# pcb_v1_mod.net
KiCad netlist of a schematic drawn in EAGLE
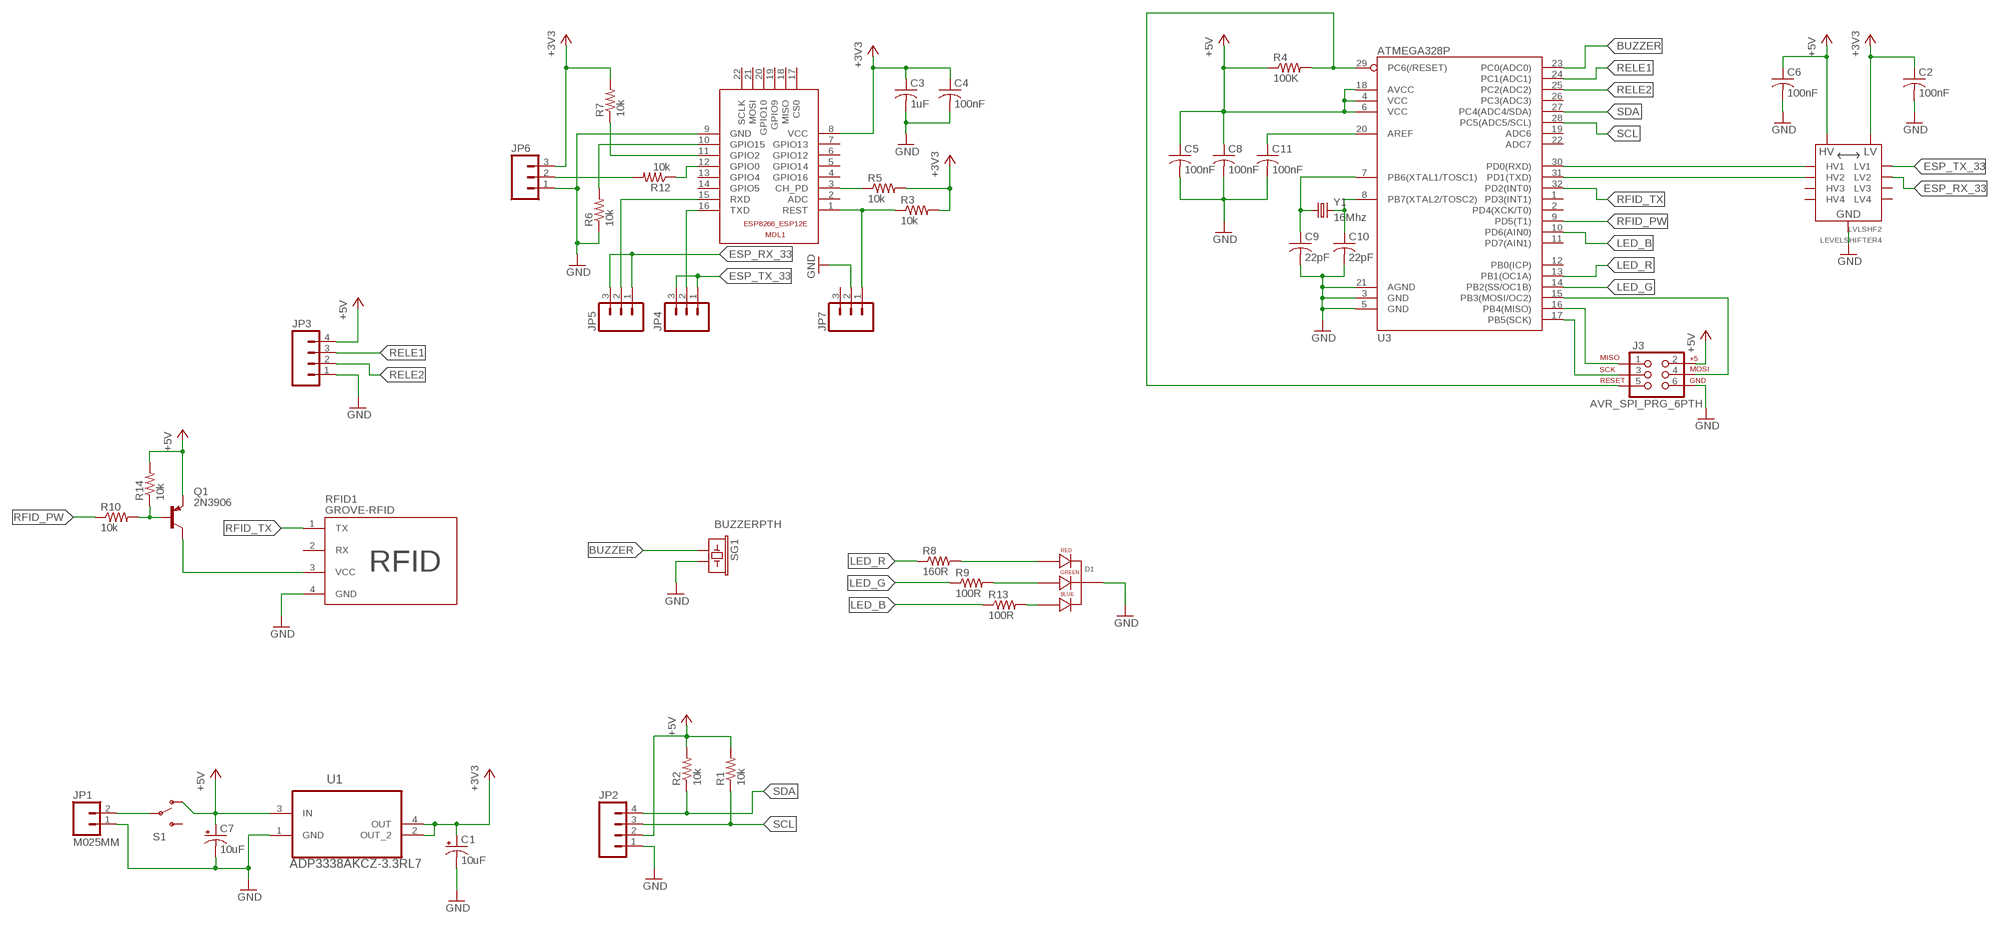
[diagram p0: schematic, sheet 1]

(export (version "E")
  (design (tool "Eeschema 10.0.6"))
  (components
    (comp (ref "C1")
      (value "10uF")
      (footprint "eagle-import:E2,5-6")
      (libsource (lib "eagle-import") (part "CPOL-USE2.5-6"))
    )
    (comp (ref "C2")
      (value "100nF")
      (footprint "eagle-import:C0805")
      (libsource (lib "eagle-import") (part "C-USC0805"))
    )
    (comp (ref "C3")
      (value "1uF")
      (footprint "eagle-import:C1206")
      (libsource (lib "eagle-import") (part "C-USC1206"))
    )
    (comp (ref "C4")
      (value "100nF")
      (footprint "eagle-import:C0805")
      (libsource (lib "eagle-import") (part "C-USC0805"))
    )
    (comp (ref "C5")
      (value "100nF")
      (footprint "eagle-import:C0805")
      (libsource (lib "eagle-import") (part "C-USC0805"))
    )
    (comp (ref "C6")
      (value "100nF")
      (footprint "eagle-import:C0805")
      (libsource (lib "eagle-import") (part "C-USC0805"))
    )
    (comp (ref "C7")
      (value "10uF")
      (footprint "eagle-import:E2,5-6")
      (libsource (lib "eagle-import") (part "CPOL-USE2.5-6"))
    )
    (comp (ref "C8")
      (value "100nF")
      (footprint "eagle-import:C0805")
      (libsource (lib "eagle-import") (part "C-USC0805"))
    )
    (comp (ref "C9")
      (value "22pF")
      (footprint "eagle-import:C1206")
      (libsource (lib "eagle-import") (part "C-USC1206"))
    )
    (comp (ref "C10")
      (value "22pF")
      (footprint "eagle-import:C1206")
      (libsource (lib "eagle-import") (part "C-USC1206"))
    )
    (comp (ref "C11")
      (value "100nF")
      (footprint "eagle-import:C0805")
      (libsource (lib "eagle-import") (part "C-USC0805"))
    )
    (comp (ref "D1")
      (value "LED-RGB-CC-THRUCLEAR")
      (footprint "eagle-import:LED-RGB-THRU")
      (libsource (lib "eagle-import") (part "LED-RGB-CC-THRUCLEAR"))
    )
    (comp (ref "J3")
      (value "AVR_SPI_PRG_6PTH")
      (footprint "eagle-import:2X3")
      (libsource (lib "eagle-import") (part "AVR_SPI_PRG_6PTH"))
    )
    (comp (ref "JP1")
      (value "M025MM")
      (footprint "eagle-import:SCREWTERMINAL-5MM-2")
      (libsource (lib "eagle-import") (part "M025MM"))
    )
    (comp (ref "JP2")
      (value "M04PTH")
      (footprint "eagle-import:1X04")
      (libsource (lib "eagle-import") (part "M04PTH"))
    )
    (comp (ref "JP3")
      (value "M04PTH")
      (footprint "eagle-import:1X04")
      (libsource (lib "eagle-import") (part "M04PTH"))
    )
    (comp (ref "JP4")
      (value "M03PTH")
      (footprint "eagle-import:1X03")
      (libsource (lib "eagle-import") (part "M03PTH"))
    )
    (comp (ref "JP5")
      (value "M03PTH")
      (footprint "eagle-import:1X03")
      (libsource (lib "eagle-import") (part "M03PTH"))
    )
    (comp (ref "JP6")
      (value "M03PTH")
      (footprint "eagle-import:1X03")
      (libsource (lib "eagle-import") (part "M03PTH"))
    )
    (comp (ref "JP7")
      (value "M03PTH")
      (footprint "eagle-import:1X03")
      (libsource (lib "eagle-import") (part "M03PTH"))
    )
    (comp (ref "LVLSHF2")
      (value "LEVELSHIFTER4")
      (footprint "eagle-import:LEVELSHIFTER4")
      (libsource (lib "eagle-import") (part "LEVELSHIFTER4"))
    )
    (comp (ref "MDL1")
      (value "ESP8266-12EESP8266-ESP12E")
      (footprint "eagle-import:ESP8266-ESP12E")
      (libsource (lib "eagle-import") (part "ESP8266-12EESP8266-ESP12E"))
    )
    (comp (ref "Q1")
      (value "2N3906")
      (footprint "eagle-import:TO92")
      (libsource (lib "eagle-import") (part "2N3906"))
    )
    (comp (ref "R1")
      (value "10k")
      (footprint "eagle-import:R0805")
      (libsource (lib "eagle-import") (part "R-US_R0805"))
    )
    (comp (ref "R2")
      (value "10k")
      (footprint "eagle-import:R0805")
      (libsource (lib "eagle-import") (part "R-US_R0805"))
    )
    (comp (ref "R3")
      (value "10k")
      (footprint "eagle-import:R0805")
      (libsource (lib "eagle-import") (part "R-US_R0805"))
    )
    (comp (ref "R4")
      (value "100K")
      (footprint "eagle-import:R0805")
      (libsource (lib "eagle-import") (part "R-US_R0805"))
    )
    (comp (ref "R5")
      (value "10k")
      (footprint "eagle-import:R0805")
      (libsource (lib "eagle-import") (part "R-US_R0805"))
    )
    (comp (ref "R6")
      (value "10k")
      (footprint "eagle-import:R0805")
      (libsource (lib "eagle-import") (part "R-US_R0805"))
    )
    (comp (ref "R7")
      (value "10k")
      (footprint "eagle-import:R0805")
      (libsource (lib "eagle-import") (part "R-US_R0805"))
    )
    (comp (ref "R8")
      (value "160R")
      (footprint "eagle-import:R1206")
      (libsource (lib "eagle-import") (part "R-US_R1206"))
    )
    (comp (ref "R9")
      (value "100R")
      (footprint "eagle-import:R0805")
      (libsource (lib "eagle-import") (part "R-US_R0805"))
    )
    (comp (ref "R10")
      (value "10k")
      (footprint "eagle-import:R0805")
      (libsource (lib "eagle-import") (part "R-US_R0805"))
    )
    (comp (ref "R12")
      (value "10k")
      (footprint "eagle-import:R0805")
      (libsource (lib "eagle-import") (part "R-US_R0805"))
    )
    (comp (ref "R13")
      (value "100R")
      (footprint "eagle-import:R0805")
      (libsource (lib "eagle-import") (part "R-US_R0805"))
    )
    (comp (ref "R14")
      (value "10k")
      (footprint "eagle-import:R0805")
      (libsource (lib "eagle-import") (part "R-US_R0805"))
    )
    (comp (ref "RFID1")
      (value "GROVE-RFID")
      (footprint "eagle-import:GROVE-RFID")
      (libsource (lib "eagle-import") (part "GROVE-RFID"))
    )
    (comp (ref "S1")
      (value "SWITCH-SPDTPTH")
      (footprint "eagle-import:SWITCH-SPDT")
      (libsource (lib "eagle-import") (part "SWITCH-SPDTPTH"))
    )
    (comp (ref "SG1")
      (value "BUZZERPTH")
      (footprint "eagle-import:BUZZER-12MM")
      (libsource (lib "eagle-import") (part "BUZZERPTH"))
    )
    (comp (ref "U1")
      (value "ADP3338AKCZ-3.3RL7")
      (footprint "eagle-import:SOT230P700X180-4N")
      (libsource (lib "eagle-import") (part "ADP3338AKCZ-3.3RL7"))
    )
    (comp (ref "U3")
      (value "ATMEGA328P")
      (footprint "eagle-import:TQFP32-08")
      (libsource (lib "eagle-import") (part "ATMEGA328_SMT"))
    )
    (comp (ref "Y1")
      (value "16Mhz")
      (footprint "eagle-import:HC49US")
      (libsource (lib "eagle-import") (part "CRYSTALHC49US"))
    )
  )
  (nets
    (net (code "1") (name "+3V3") (class "Default")
      (node (ref "C1") (pin "+") (pinfunction "+_+") (pintype "passive"))
      (node (ref "C2") (pin "1") (pinfunction "1_1") (pintype "passive"))
      (node (ref "C3") (pin "1") (pinfunction "1_1") (pintype "passive"))
      (node (ref "C4") (pin "1") (pinfunction "1_1") (pintype "passive"))
      (node (ref "JP6") (pin "3") (pinfunction "3_3") (pintype "passive"))
      (node (ref "LVLSHF2") (pin "LV") (pinfunction "LV_LV") (pintype "power_in"))
      (node (ref "MDL1") (pin "8") (pinfunction "VCC_8") (pintype "bidirectional"))
      (node (ref "R3") (pin "2") (pinfunction "2_2") (pintype "passive"))
      (node (ref "R5") (pin "2") (pinfunction "2_2") (pintype "passive"))
      (node (ref "R7") (pin "2") (pinfunction "2_2") (pintype "passive"))
      (node (ref "U1") (pin "2") (pinfunction "OUT_2_2") (pintype "output"))
      (node (ref "U1") (pin "4") (pinfunction "OUT_4") (pintype "output"))
    )
    (net (code "2") (name "+5V") (class "Default")
      (node (ref "C5") (pin "1") (pinfunction "1_1") (pintype "passive"))
      (node (ref "C6") (pin "1") (pinfunction "1_1") (pintype "passive"))
      (node (ref "C7") (pin "+") (pinfunction "+_+") (pintype "passive"))
      (node (ref "C8") (pin "1") (pinfunction "1_1") (pintype "passive"))
      (node (ref "J3") (pin "2") (pinfunction "2_2") (pintype "passive"))
      (node (ref "JP2") (pin "2") (pinfunction "2_2") (pintype "passive"))
      (node (ref "JP3") (pin "4") (pinfunction "4_4") (pintype "passive"))
      (node (ref "LVLSHF2") (pin "HV") (pinfunction "HV_HV") (pintype "power_in"))
      (node (ref "Q1") (pin "3") (pinfunction "E_3") (pintype "passive"))
      (node (ref "R1") (pin "2") (pinfunction "2_2") (pintype "passive"))
      (node (ref "R14") (pin "2") (pinfunction "2_2") (pintype "passive"))
      (node (ref "R2") (pin "2") (pinfunction "2_2") (pintype "passive"))
      (node (ref "R4") (pin "1") (pinfunction "1_1") (pintype "passive"))
      (node (ref "S1") (pin "1") (pinfunction "O_1") (pintype "passive"))
      (node (ref "U1") (pin "3") (pinfunction "IN_3") (pintype "input"))
      (node (ref "U3") (pin "18") (pinfunction "AVCC_18") (pintype "bidirectional"))
      (node (ref "U3") (pin "4") (pinfunction "VCC_4") (pintype "bidirectional"))
      (node (ref "U3") (pin "6") (pinfunction "VCC_6") (pintype "bidirectional"))
    )
    (net (code "3") (name "BUZZER") (class "Default")
      (node (ref "SG1") (pin "+") (pinfunction "1_+") (pintype "passive"))
      (node (ref "U3") (pin "23") (pinfunction "PC0(ADC0)_23") (pintype "bidirectional"))
    )
    (net (code "4") (name "ESP_RX_33") (class "Default")
      (node (ref "JP5") (pin "1") (pinfunction "1_1") (pintype "passive"))
      (node (ref "JP5") (pin "3") (pinfunction "3_3") (pintype "passive"))
      (node (ref "LVLSHF2") (pin "LV2") (pinfunction "LV2_LV2") (pintype "bidirectional"))
    )
    (net (code "5") (name "ESP_TX_33") (class "Default")
      (node (ref "JP4") (pin "1") (pinfunction "1_1") (pintype "passive"))
      (node (ref "JP4") (pin "3") (pinfunction "3_3") (pintype "passive"))
      (node (ref "LVLSHF2") (pin "LV1") (pinfunction "LV1_LV1") (pintype "bidirectional"))
    )
    (net (code "6") (name "GND") (class "Default")
      (node (ref "C1") (pin "-") (pinfunction "-_-") (pintype "passive"))
      (node (ref "C10") (pin "2") (pinfunction "2_2") (pintype "passive"))
      (node (ref "C11") (pin "2") (pinfunction "2_2") (pintype "passive"))
      (node (ref "C2") (pin "2") (pinfunction "2_2") (pintype "passive"))
      (node (ref "C3") (pin "2") (pinfunction "2_2") (pintype "passive"))
      (node (ref "C4") (pin "2") (pinfunction "2_2") (pintype "passive"))
      (node (ref "C5") (pin "2") (pinfunction "2_2") (pintype "passive"))
      (node (ref "C6") (pin "2") (pinfunction "2_2") (pintype "passive"))
      (node (ref "C7") (pin "-") (pinfunction "-_-") (pintype "passive"))
      (node (ref "C8") (pin "2") (pinfunction "2_2") (pintype "passive"))
      (node (ref "C9") (pin "2") (pinfunction "2_2") (pintype "passive"))
      (node (ref "D1") (pin "2") (pinfunction "CATHODE_2") (pintype "bidirectional"))
      (node (ref "J3") (pin "6") (pinfunction "6_6") (pintype "passive"))
      (node (ref "JP1") (pin "1") (pinfunction "1_1") (pintype "passive"))
      (node (ref "JP2") (pin "1") (pinfunction "1_1") (pintype "passive"))
      (node (ref "JP3") (pin "1") (pinfunction "1_1") (pintype "passive"))
      (node (ref "JP6") (pin "1") (pinfunction "1_1") (pintype "passive"))
      (node (ref "JP7") (pin "2") (pinfunction "2_2") (pintype "passive"))
      (node (ref "LVLSHF2") (pin "GND") (pinfunction "GND_GND") (pintype "bidirectional"))
      (node (ref "LVLSHF2") (pin "GND1") (pinfunction "GND_GND1") (pintype "bidirectional"))
      (node (ref "MDL1") (pin "9") (pinfunction "GND_9") (pintype "bidirectional"))
      (node (ref "R6") (pin "1") (pinfunction "1_1") (pintype "passive"))
      (node (ref "RFID1") (pin "4") (pinfunction "GND_4") (pintype "bidirectional"))
      (node (ref "SG1") (pin "-") (pinfunction "2_-") (pintype "passive"))
      (node (ref "U1") (pin "1") (pinfunction "GND_1") (pintype "passive"))
      (node (ref "U3") (pin "21") (pinfunction "AGND_21") (pintype "bidirectional"))
      (node (ref "U3") (pin "3") (pinfunction "GND_3") (pintype "bidirectional"))
      (node (ref "U3") (pin "5") (pinfunction "GND_5") (pintype "bidirectional"))
    )
    (net (code "7") (name "LED_B") (class "Default")
      (node (ref "R13") (pin "1") (pinfunction "1_1") (pintype "passive"))
      (node (ref "U3") (pin "10") (pinfunction "PD6(AIN0)_10") (pintype "bidirectional"))
    )
    (net (code "8") (name "LED_G") (class "Default")
      (node (ref "R9") (pin "1") (pinfunction "1_1") (pintype "passive"))
      (node (ref "U3") (pin "14") (pinfunction "PB2(SS/OC1B)_14") (pintype "bidirectional"))
    )
    (net (code "9") (name "LED_R") (class "Default")
      (node (ref "R8") (pin "1") (pinfunction "1_1") (pintype "passive"))
      (node (ref "U3") (pin "13") (pinfunction "PB1(OC1A)_13") (pintype "bidirectional"))
    )
    (net (code "10") (name "Net-(D1-BLUE_CATHODE)") (class "Default")
      (node (ref "D1") (pin "4") (pinfunction "BLUE_CATHODE_4") (pintype "bidirectional"))
      (node (ref "R13") (pin "2") (pinfunction "2_2") (pintype "passive"))
    )
    (net (code "11") (name "Net-(D1-GREEN_CATHODE)") (class "Default")
      (node (ref "D1") (pin "3") (pinfunction "GREEN_CATHODE_3") (pintype "bidirectional"))
      (node (ref "R9") (pin "2") (pinfunction "2_2") (pintype "passive"))
    )
    (net (code "12") (name "Net-(D1-RED_CATHODE)") (class "Default")
      (node (ref "D1") (pin "1") (pinfunction "RED_CATHODE_1") (pintype "bidirectional"))
      (node (ref "R8") (pin "2") (pinfunction "2_2") (pintype "passive"))
    )
    (net (code "13") (name "Net-(JP6-Pad2)") (class "Default")
      (node (ref "JP6") (pin "2") (pinfunction "2_2") (pintype "passive"))
      (node (ref "R12") (pin "2") (pinfunction "2_2") (pintype "passive"))
    )
    (net (code "14") (name "Net-(MDL1-CH_PD)") (class "Default")
      (node (ref "MDL1") (pin "3") (pinfunction "CH_PD_3") (pintype "bidirectional"))
      (node (ref "R5") (pin "1") (pinfunction "1_1") (pintype "passive"))
    )
    (net (code "15") (name "Net-(MDL1-GPIO0)") (class "Default")
      (node (ref "MDL1") (pin "12") (pinfunction "GPIO0_12") (pintype "bidirectional"))
      (node (ref "R12") (pin "1") (pinfunction "1_1") (pintype "passive"))
    )
    (net (code "16") (name "Net-(MDL1-GPIO2)") (class "Default")
      (node (ref "MDL1") (pin "11") (pinfunction "GPIO2_11") (pintype "bidirectional"))
      (node (ref "R7") (pin "1") (pinfunction "1_1") (pintype "passive"))
    )
    (net (code "17") (name "Net-(MDL1-GPIO15)") (class "Default")
      (node (ref "MDL1") (pin "10") (pinfunction "GPIO15_10") (pintype "bidirectional"))
      (node (ref "R6") (pin "2") (pinfunction "2_2") (pintype "passive"))
    )
    (net (code "18") (name "Net-(MDL1-REST)") (class "Default")
      (node (ref "JP7") (pin "1") (pinfunction "1_1") (pintype "passive"))
      (node (ref "MDL1") (pin "1") (pinfunction "REST_1") (pintype "bidirectional"))
      (node (ref "R3") (pin "1") (pinfunction "1_1") (pintype "passive"))
    )
    (net (code "19") (name "Net-(MDL1-RXD)") (class "Default")
      (node (ref "JP5") (pin "2") (pinfunction "2_2") (pintype "passive"))
      (node (ref "MDL1") (pin "15") (pinfunction "RXD_15") (pintype "bidirectional"))
    )
    (net (code "20") (name "Net-(MDL1-TXD)") (class "Default")
      (node (ref "JP4") (pin "2") (pinfunction "2_2") (pintype "passive"))
      (node (ref "MDL1") (pin "16") (pinfunction "TXD_16") (pintype "bidirectional"))
    )
    (net (code "21") (name "Net-(Q1-B)") (class "Default")
      (node (ref "Q1") (pin "2") (pinfunction "B_2") (pintype "passive"))
      (node (ref "R10") (pin "2") (pinfunction "2_2") (pintype "passive"))
      (node (ref "R14") (pin "1") (pinfunction "1_1") (pintype "passive"))
    )
    (net (code "22") (name "Net-(Q1-C)") (class "Default")
      (node (ref "Q1") (pin "1") (pinfunction "C_1") (pintype "passive"))
      (node (ref "RFID1") (pin "3") (pinfunction "VCC_3") (pintype "bidirectional"))
    )
    (net (code "23") (name "Net-(S1-P)") (class "Default")
      (node (ref "JP1") (pin "2") (pinfunction "2_2") (pintype "passive"))
      (node (ref "S1") (pin "2") (pinfunction "P_2") (pintype "passive"))
    )
    (net (code "24") (name "Net-(U3-AREF)") (class "Default")
      (node (ref "C11") (pin "1") (pinfunction "1_1") (pintype "passive"))
      (node (ref "U3") (pin "20") (pinfunction "AREF_20") (pintype "bidirectional"))
    )
    (net (code "25") (name "Net-(U3-PB3(MOSI{slash}OC2))") (class "Default")
      (node (ref "J3") (pin "4") (pinfunction "4_4") (pintype "passive"))
      (node (ref "U3") (pin "15") (pinfunction "PB3(MOSI/OC2)_15") (pintype "bidirectional"))
    )
    (net (code "26") (name "Net-(U3-PB4(MISO))") (class "Default")
      (node (ref "J3") (pin "1") (pinfunction "1_1") (pintype "passive"))
      (node (ref "U3") (pin "16") (pinfunction "PB4(MISO)_16") (pintype "bidirectional"))
    )
    (net (code "27") (name "Net-(U3-PB5(SCK))") (class "Default")
      (node (ref "J3") (pin "3") (pinfunction "3_3") (pintype "passive"))
      (node (ref "U3") (pin "17") (pinfunction "PB5(SCK)_17") (pintype "bidirectional"))
    )
    (net (code "28") (name "Net-(U3-PB6(XTAL1{slash}TOSC1))") (class "Default")
      (node (ref "C9") (pin "1") (pinfunction "1_1") (pintype "passive"))
      (node (ref "U3") (pin "7") (pinfunction "PB6(XTAL1/TOSC1)_7") (pintype "bidirectional"))
      (node (ref "Y1") (pin "1") (pinfunction "1_1") (pintype "passive"))
    )
    (net (code "29") (name "Net-(U3-PB7(XTAL2{slash}TOSC2))") (class "Default")
      (node (ref "C10") (pin "1") (pinfunction "1_1") (pintype "passive"))
      (node (ref "U3") (pin "8") (pinfunction "PB7(XTAL2/TOSC2)_8") (pintype "bidirectional"))
      (node (ref "Y1") (pin "2") (pinfunction "2_2") (pintype "passive"))
    )
    (net (code "30") (name "Net-(U3-PC6({slash}RESET))") (class "Default")
      (node (ref "J3") (pin "5") (pinfunction "5_5") (pintype "passive"))
      (node (ref "R4") (pin "2") (pinfunction "2_2") (pintype "passive"))
      (node (ref "U3") (pin "29") (pinfunction "PC6(/RESET)_29") (pintype "bidirectional"))
    )
    (net (code "31") (name "Net-(U3-PD0(RXD))") (class "Default")
      (node (ref "LVLSHF2") (pin "HV1") (pinfunction "HV1_HV1") (pintype "bidirectional"))
      (node (ref "U3") (pin "30") (pinfunction "PD0(RXD)_30") (pintype "bidirectional"))
    )
    (net (code "32") (name "Net-(U3-PD1(TXD))") (class "Default")
      (node (ref "LVLSHF2") (pin "HV2") (pinfunction "HV2_HV2") (pintype "bidirectional"))
      (node (ref "U3") (pin "31") (pinfunction "PD1(TXD)_31") (pintype "bidirectional"))
    )
    (net (code "33") (name "RELE1") (class "Default")
      (node (ref "JP3") (pin "3") (pinfunction "3_3") (pintype "passive"))
      (node (ref "U3") (pin "24") (pinfunction "PC1(ADC1)_24") (pintype "bidirectional"))
    )
    (net (code "34") (name "RELE2") (class "Default")
      (node (ref "JP3") (pin "2") (pinfunction "2_2") (pintype "passive"))
      (node (ref "U3") (pin "25") (pinfunction "PC2(ADC2)_25") (pintype "bidirectional"))
    )
    (net (code "35") (name "RFID_PW") (class "Default")
      (node (ref "R10") (pin "1") (pinfunction "1_1") (pintype "passive"))
      (node (ref "U3") (pin "9") (pinfunction "PD5(T1)_9") (pintype "bidirectional"))
    )
    (net (code "36") (name "RFID_TX") (class "Default")
      (node (ref "RFID1") (pin "1") (pinfunction "TX_1") (pintype "bidirectional"))
      (node (ref "U3") (pin "32") (pinfunction "PD2(INT0)_32") (pintype "bidirectional"))
    )
    (net (code "37") (name "SCL") (class "Default")
      (node (ref "JP2") (pin "3") (pinfunction "3_3") (pintype "passive"))
      (node (ref "R1") (pin "1") (pinfunction "1_1") (pintype "passive"))
      (node (ref "U3") (pin "28") (pinfunction "PC5(ADC5/SCL)_28") (pintype "bidirectional"))
    )
    (net (code "38") (name "SDA") (class "Default")
      (node (ref "JP2") (pin "4") (pinfunction "4_4") (pintype "passive"))
      (node (ref "R2") (pin "1") (pinfunction "1_1") (pintype "passive"))
      (node (ref "U3") (pin "27") (pinfunction "PC4(ADC4/SDA)_27") (pintype "bidirectional"))
    )
    (net (code "39") (name "unconnected-(JP7-Pad3)") (class "Default")
      (node (ref "JP7") (pin "3") (pinfunction "3_3") (pintype "passive"))
    )
    (net (code "40") (name "unconnected-(LVLSHF2-PadHV3)") (class "Default")
      (node (ref "LVLSHF2") (pin "HV3") (pinfunction "HV3_HV3") (pintype "input"))
    )
    (net (code "41") (name "unconnected-(LVLSHF2-PadHV4)") (class "Default")
      (node (ref "LVLSHF2") (pin "HV4") (pinfunction "HV4_HV4") (pintype "input"))
    )
    (net (code "42") (name "unconnected-(LVLSHF2-PadLV3)") (class "Default")
      (node (ref "LVLSHF2") (pin "LV3") (pinfunction "LV3_LV3") (pintype "output"))
    )
    (net (code "43") (name "unconnected-(LVLSHF2-PadLV4)") (class "Default")
      (node (ref "LVLSHF2") (pin "LV4") (pinfunction "LV4_LV4") (pintype "output"))
    )
    (net (code "44") (name "unconnected-(MDL1-ADC-Pad2)") (class "Default")
      (node (ref "MDL1") (pin "2") (pinfunction "ADC_2") (pintype "bidirectional"))
    )
    (net (code "45") (name "unconnected-(MDL1-CS0-Pad17)") (class "Default")
      (node (ref "MDL1") (pin "17") (pinfunction "CS0_17") (pintype "bidirectional"))
    )
    (net (code "46") (name "unconnected-(MDL1-GPIO4-Pad13)") (class "Default")
      (node (ref "MDL1") (pin "13") (pinfunction "GPIO4_13") (pintype "bidirectional"))
    )
    (net (code "47") (name "unconnected-(MDL1-GPIO5-Pad14)") (class "Default")
      (node (ref "MDL1") (pin "14") (pinfunction "GPIO5_14") (pintype "bidirectional"))
    )
    (net (code "48") (name "unconnected-(MDL1-GPIO9-Pad19)") (class "Default")
      (node (ref "MDL1") (pin "19") (pinfunction "GPIO9_19") (pintype "bidirectional"))
    )
    (net (code "49") (name "unconnected-(MDL1-GPIO10-Pad20)") (class "Default")
      (node (ref "MDL1") (pin "20") (pinfunction "GPIO10_20") (pintype "bidirectional"))
    )
    (net (code "50") (name "unconnected-(MDL1-GPIO12-Pad6)") (class "Default")
      (node (ref "MDL1") (pin "6") (pinfunction "GPIO12_6") (pintype "bidirectional"))
    )
    (net (code "51") (name "unconnected-(MDL1-GPIO13-Pad7)") (class "Default")
      (node (ref "MDL1") (pin "7") (pinfunction "GPIO13_7") (pintype "bidirectional"))
    )
    (net (code "52") (name "unconnected-(MDL1-GPIO14-Pad5)") (class "Default")
      (node (ref "MDL1") (pin "5") (pinfunction "GPIO14_5") (pintype "bidirectional"))
    )
    (net (code "53") (name "unconnected-(MDL1-GPIO16-Pad4)") (class "Default")
      (node (ref "MDL1") (pin "4") (pinfunction "GPIO16_4") (pintype "bidirectional"))
    )
    (net (code "54") (name "unconnected-(MDL1-MISO-Pad18)") (class "Default")
      (node (ref "MDL1") (pin "18") (pinfunction "MISO_18") (pintype "bidirectional"))
    )
    (net (code "55") (name "unconnected-(MDL1-MOSI-Pad21)") (class "Default")
      (node (ref "MDL1") (pin "21") (pinfunction "MOSI_21") (pintype "bidirectional"))
    )
    (net (code "56") (name "unconnected-(MDL1-SCLK-Pad22)") (class "Default")
      (node (ref "MDL1") (pin "22") (pinfunction "SCLK_22") (pintype "bidirectional"))
    )
    (net (code "57") (name "unconnected-(RFID1-RX-Pad2)") (class "Default")
      (node (ref "RFID1") (pin "2") (pinfunction "RX_2") (pintype "bidirectional"))
    )
    (net (code "58") (name "unconnected-(S1-S-Pad3)") (class "Default")
      (node (ref "S1") (pin "3") (pinfunction "S_3") (pintype "passive"))
    )
    (net (code "59") (name "unconnected-(U3-ADC6-Pad19)") (class "Default")
      (node (ref "U3") (pin "19") (pinfunction "ADC6_19") (pintype "bidirectional"))
    )
    (net (code "60") (name "unconnected-(U3-ADC7-Pad22)") (class "Default")
      (node (ref "U3") (pin "22") (pinfunction "ADC7_22") (pintype "bidirectional"))
    )
    (net (code "61") (name "unconnected-(U3-PB0(ICP)-Pad12)") (class "Default")
      (node (ref "U3") (pin "12") (pinfunction "PB0(ICP)_12") (pintype "bidirectional"))
    )
    (net (code "62") (name "unconnected-(U3-PC3(ADC3)-Pad26)") (class "Default")
      (node (ref "U3") (pin "26") (pinfunction "PC3(ADC3)_26") (pintype "bidirectional"))
    )
    (net (code "63") (name "unconnected-(U3-PD3(INT1)-Pad1)") (class "Default")
      (node (ref "U3") (pin "1") (pinfunction "PD3(INT1)_1") (pintype "bidirectional"))
    )
    (net (code "64") (name "unconnected-(U3-PD4(XCK{slash}T0)-Pad2)") (class "Default")
      (node (ref "U3") (pin "2") (pinfunction "PD4(XCK/T0)_2") (pintype "bidirectional"))
    )
    (net (code "65") (name "unconnected-(U3-PD7(AIN1)-Pad11)") (class "Default")
      (node (ref "U3") (pin "11") (pinfunction "PD7(AIN1)_11") (pintype "bidirectional"))
    )
  )
)
